# Ultrasonic.net
KiCad netlist of a schematic drawn in EAGLE
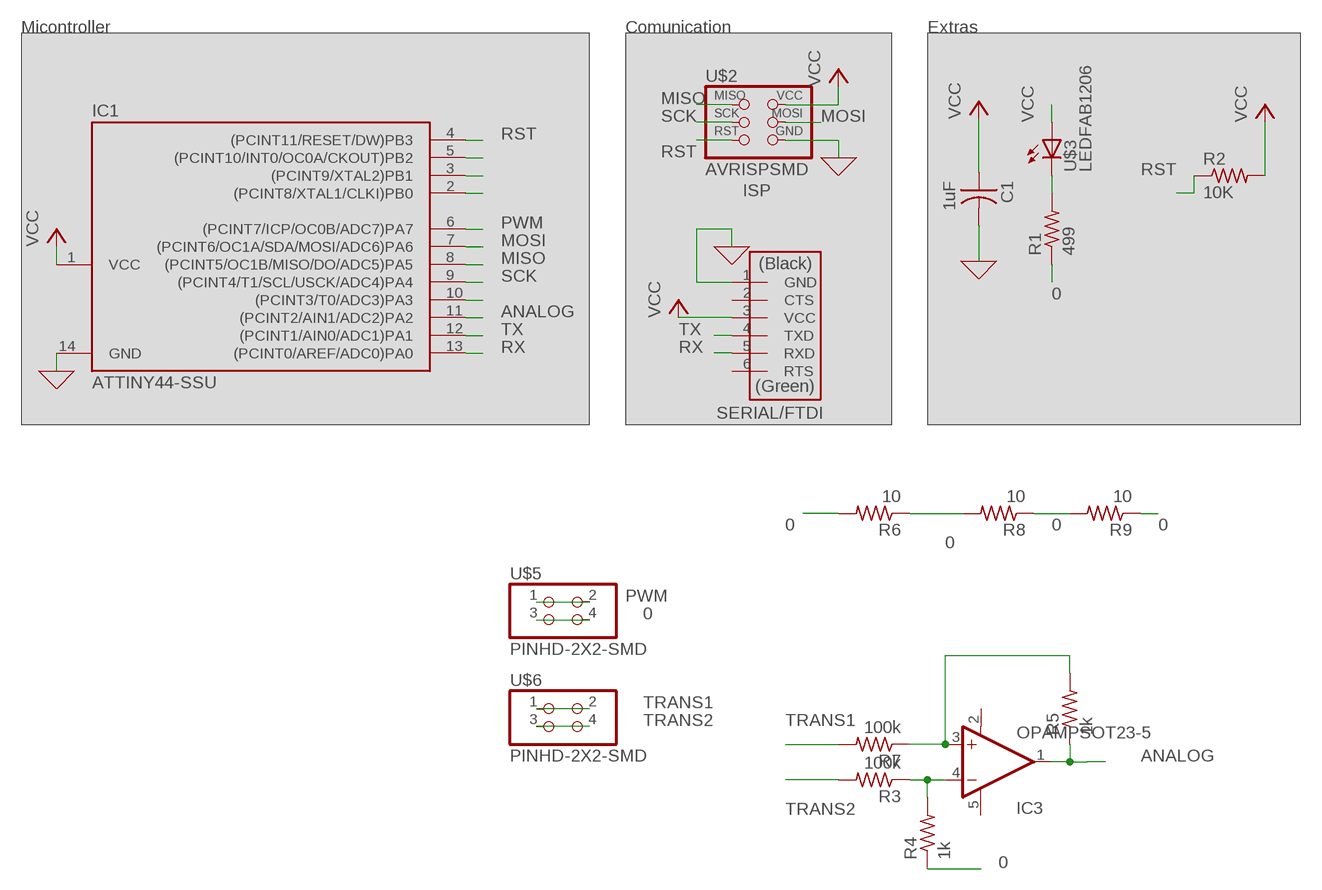
[diagram p0: schematic, sheet 1]

(export (version "E")
  (design (tool "Eeschema 10.0.6"))
  (components
    (comp (ref "C1")
      (value "1uF")
      (footprint "eagle-import:C1206FAB")
      (libsource (lib "eagle-import") (part "CAP-US1206FAB"))
    )
    (comp (ref "IC1")
      (value "ATTINY44-SSU")
      (footprint "eagle-import:SOIC14")
      (libsource (lib "eagle-import") (part "ATTINY44-SSU"))
    )
    (comp (ref "IC3")
      (value "OPAMPSOT23-5")
      (footprint "eagle-import:SOT23-5")
      (libsource (lib "eagle-import") (part "OPAMPSOT23-5"))
    )
    (comp (ref "R1")
      (value "499")
      (footprint "eagle-import:R1206FAB")
      (libsource (lib "eagle-import") (part "RES-US1206FAB"))
    )
    (comp (ref "R2")
      (value "10K")
      (footprint "eagle-import:R1206FAB")
      (libsource (lib "eagle-import") (part "RES-US1206FAB"))
    )
    (comp (ref "R3")
      (value "100k")
      (footprint "eagle-import:R1206FAB")
      (libsource (lib "eagle-import") (part "RES-US1206FAB"))
    )
    (comp (ref "R4")
      (value "1k")
      (footprint "eagle-import:R1206FAB")
      (libsource (lib "eagle-import") (part "RES-US1206FAB"))
    )
    (comp (ref "R5")
      (value "1k")
      (footprint "eagle-import:R1206FAB")
      (libsource (lib "eagle-import") (part "RES-US1206FAB"))
    )
    (comp (ref "R6")
      (value "10")
      (footprint "eagle-import:R1206FAB")
      (libsource (lib "eagle-import") (part "RES-US1206FAB"))
    )
    (comp (ref "R7")
      (value "100k")
      (footprint "eagle-import:R1206FAB")
      (libsource (lib "eagle-import") (part "RES-US1206FAB"))
    )
    (comp (ref "R8")
      (value "10")
      (footprint "eagle-import:R1206FAB")
      (libsource (lib "eagle-import") (part "RES-US1206FAB"))
    )
    (comp (ref "R9")
      (value "10")
      (footprint "eagle-import:R1206FAB")
      (libsource (lib "eagle-import") (part "RES-US1206FAB"))
    )
    (comp (ref "U$1")
      (value "FTDI-SMD-HEADER")
      (footprint "eagle-import:1X06SMD")
      (libsource (lib "eagle-import") (part "FTDI-SMD-HEADER"))
    )
    (comp (ref "U$2")
      (value "AVRISPSMD")
      (footprint "eagle-import:2X03SMD")
      (libsource (lib "eagle-import") (part "AVRISPSMD"))
    )
    (comp (ref "U$3")
      (value "LEDFAB1206")
      (footprint "eagle-import:LED1206FAB")
      (libsource (lib "eagle-import") (part "LEDFAB1206"))
    )
    (comp (ref "U$5")
      (value "PINHD-2X2-SMD")
      (footprint "eagle-import:2X02SMD")
      (libsource (lib "eagle-import") (part "PINHD-2X2-SMD"))
    )
    (comp (ref "U$6")
      (value "PINHD-2X2-SMD")
      (footprint "eagle-import:2X02SMD")
      (libsource (lib "eagle-import") (part "PINHD-2X2-SMD"))
    )
  )
  (nets
    (net (code "1") (name "/ANALOG") (class "Default")
      (node (ref "IC1") (pin "11") (pinfunction "(PCINT2/AIN1/ADC2)PA2_11") (pintype "bidirectional"))
      (node (ref "IC3") (pin "1") (pinfunction "OUT_1") (pintype "output"))
      (node (ref "R5") (pin "1") (pinfunction "1_1") (pintype "passive"))
    )
    (net (code "2") (name "/MISO") (class "Default")
      (node (ref "IC1") (pin "8") (pinfunction "(PCINT5/OC1B/MISO/DO/ADC5)PA5_8") (pintype "bidirectional"))
      (node (ref "U$2") (pin "1") (pinfunction "MISO_1") (pintype "passive"))
    )
    (net (code "3") (name "/MOSI") (class "Default")
      (node (ref "IC1") (pin "7") (pinfunction "(PCINT6/OC1A/SDA/MOSI/ADC6)PA6_7") (pintype "bidirectional"))
      (node (ref "U$2") (pin "4") (pinfunction "MOSI_4") (pintype "passive"))
    )
    (net (code "4") (name "/PWM") (class "Default")
      (node (ref "IC1") (pin "6") (pinfunction "(PCINT7/ICP/OC0B/ADC7)PA7_6") (pintype "bidirectional"))
      (node (ref "U$5") (pin "1") (pinfunction "1_1") (pintype "passive"))
      (node (ref "U$5") (pin "2") (pinfunction "2_2") (pintype "passive"))
    )
    (net (code "5") (name "/RST") (class "Default")
      (node (ref "IC1") (pin "4") (pinfunction "(PCINT11/RESET/DW)PB3_4") (pintype "bidirectional"))
      (node (ref "R2") (pin "1") (pinfunction "1_1") (pintype "passive"))
      (node (ref "U$2") (pin "5") (pinfunction "RST_5") (pintype "passive"))
    )
    (net (code "6") (name "/RX") (class "Default")
      (node (ref "IC1") (pin "13") (pinfunction "(PCINT0/AREF/ADC0)PA0_13") (pintype "bidirectional"))
      (node (ref "U$1") (pin "5") (pinfunction "RXD_5") (pintype "bidirectional"))
    )
    (net (code "7") (name "/SCK") (class "Default")
      (node (ref "IC1") (pin "9") (pinfunction "(PCINT4/T1/SCL/USCK/ADC4)PA4_9") (pintype "bidirectional"))
      (node (ref "U$2") (pin "3") (pinfunction "SCK_3") (pintype "passive"))
    )
    (net (code "8") (name "/TRANS1") (class "Default")
      (node (ref "R7") (pin "2") (pinfunction "2_2") (pintype "passive"))
      (node (ref "U$6") (pin "1") (pinfunction "1_1") (pintype "passive"))
      (node (ref "U$6") (pin "2") (pinfunction "2_2") (pintype "passive"))
    )
    (net (code "9") (name "/TRANS2") (class "Default")
      (node (ref "R3") (pin "2") (pinfunction "2_2") (pintype "passive"))
      (node (ref "U$6") (pin "3") (pinfunction "3_3") (pintype "passive"))
      (node (ref "U$6") (pin "4") (pinfunction "4_4") (pintype "passive"))
    )
    (net (code "10") (name "/TX") (class "Default")
      (node (ref "IC1") (pin "12") (pinfunction "(PCINT1/AIN0/ADC1)PA1_12") (pintype "bidirectional"))
      (node (ref "U$1") (pin "4") (pinfunction "TXD_4") (pintype "bidirectional"))
    )
    (net (code "11") (name "/V+") (class "Default")
      (node (ref "IC3") (pin "5") (pinfunction "V+_5") (pintype "power_in"))
    )
    (net (code "12") (name "/V-") (class "Default")
      (node (ref "IC3") (pin "2") (pinfunction "V-_2") (pintype "power_in"))
    )
    (net (code "13") (name "GND") (class "Default")
      (node (ref "C1") (pin "2") (pinfunction "2_2") (pintype "passive"))
      (node (ref "IC1") (pin "14") (pinfunction "GND_14") (pintype "power_in"))
      (node (ref "R1") (pin "1") (pinfunction "1_1") (pintype "passive"))
      (node (ref "R4") (pin "1") (pinfunction "1_1") (pintype "passive"))
      (node (ref "R6") (pin "1") (pinfunction "1_1") (pintype "passive"))
      (node (ref "R6") (pin "2") (pinfunction "2_2") (pintype "passive"))
      (node (ref "R8") (pin "1") (pinfunction "1_1") (pintype "passive"))
      (node (ref "R8") (pin "2") (pinfunction "2_2") (pintype "passive"))
      (node (ref "R9") (pin "1") (pinfunction "1_1") (pintype "passive"))
      (node (ref "R9") (pin "2") (pinfunction "2_2") (pintype "passive"))
      (node (ref "U$1") (pin "1") (pinfunction "GND_1") (pintype "bidirectional"))
      (node (ref "U$2") (pin "6") (pinfunction "GND_6") (pintype "passive"))
      (node (ref "U$5") (pin "3") (pinfunction "3_3") (pintype "passive"))
      (node (ref "U$5") (pin "4") (pinfunction "4_4") (pintype "passive"))
    )
    (net (code "14") (name "Net-(IC3-+IN)") (class "Default")
      (node (ref "IC3") (pin "3") (pinfunction "+IN_3") (pintype "input"))
      (node (ref "R5") (pin "2") (pinfunction "2_2") (pintype "passive"))
      (node (ref "R7") (pin "1") (pinfunction "1_1") (pintype "passive"))
    )
    (net (code "15") (name "Net-(IC3--IN)") (class "Default")
      (node (ref "IC3") (pin "4") (pinfunction "-IN_4") (pintype "input"))
      (node (ref "R3") (pin "1") (pinfunction "1_1") (pintype "passive"))
      (node (ref "R4") (pin "2") (pinfunction "2_2") (pintype "passive"))
    )
    (net (code "16") (name "Net-(U$3-C)") (class "Default")
      (node (ref "R1") (pin "2") (pinfunction "2_2") (pintype "passive"))
      (node (ref "U$3") (pin "2") (pinfunction "C_2") (pintype "passive"))
    )
    (net (code "17") (name "VCC") (class "Default")
      (node (ref "C1") (pin "1") (pinfunction "1_1") (pintype "passive"))
      (node (ref "IC1") (pin "1") (pinfunction "VCC_1") (pintype "power_in"))
      (node (ref "R2") (pin "2") (pinfunction "2_2") (pintype "passive"))
      (node (ref "U$1") (pin "3") (pinfunction "VCC_3") (pintype "bidirectional"))
      (node (ref "U$2") (pin "2") (pinfunction "VCC_2") (pintype "passive"))
      (node (ref "U$3") (pin "1") (pinfunction "A_1") (pintype "passive"))
    )
    (net (code "18") (name "unconnected-(IC1-(PCINT3{slash}T0{slash}ADC3)PA3-Pad10)") (class "Default")
      (node (ref "IC1") (pin "10") (pinfunction "(PCINT3/T0/ADC3)PA3_10") (pintype "bidirectional"))
    )
    (net (code "19") (name "unconnected-(IC1-(PCINT8{slash}XTAL1{slash}CLKI)PB0-Pad2)") (class "Default")
      (node (ref "IC1") (pin "2") (pinfunction "(PCINT8/XTAL1/CLKI)PB0_2") (pintype "bidirectional"))
    )
    (net (code "20") (name "unconnected-(IC1-(PCINT9{slash}XTAL2)PB1-Pad3)") (class "Default")
      (node (ref "IC1") (pin "3") (pinfunction "(PCINT9/XTAL2)PB1_3") (pintype "bidirectional"))
    )
    (net (code "21") (name "unconnected-(IC1-(PCINT10{slash}INT0{slash}OC0A{slash}CKOUT)PB2-Pad5)") (class "Default")
      (node (ref "IC1") (pin "5") (pinfunction "(PCINT10/INT0/OC0A/CKOUT)PB2_5") (pintype "bidirectional"))
    )
    (net (code "22") (name "unconnected-(U$1-CTS-Pad2)") (class "Default")
      (node (ref "U$1") (pin "2") (pinfunction "CTS_2") (pintype "bidirectional"))
    )
    (net (code "23") (name "unconnected-(U$1-RTS-Pad6)") (class "Default")
      (node (ref "U$1") (pin "6") (pinfunction "RTS_6") (pintype "bidirectional"))
    )
  )
)
